# computer.net
KiCad netlist of a schematic drawn in Altium Designer
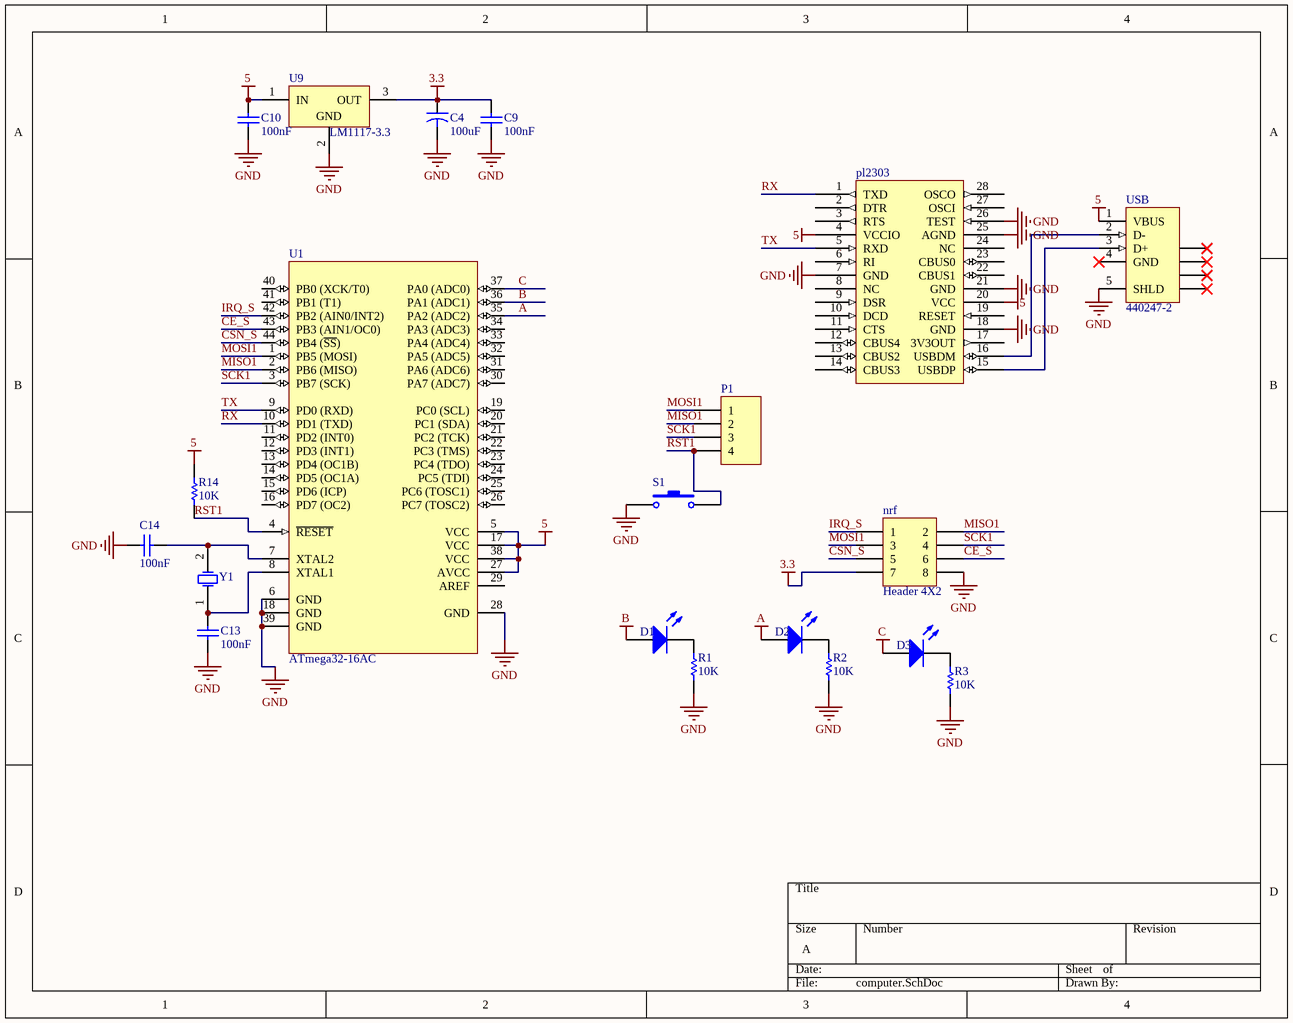
[diagram p0: computer.SchDoc]

(export (version "E")
  (design (tool "Eeschema 10.0.6"))
  (components
    (comp (ref "C4")
      (value "100uF")
      (footprint "cap")
      (description "Capacitor")
      (fields (field (name "Comment") "Cap2") (field (name "PUBLISHER") "Altium Limited"))
      (libsource (lib "Miscellaneous Devices") (part "Cap2"))
    )
    (comp (ref "C9")
      (value "100nF")
      (footprint "H1X02F")
      (description "Capacitor")
      (fields (field (name "Comment") "Cap") (field (name "PUBLISHER") "Altium Limited"))
      (libsource (lib "Miscellaneous Devices") (part "Cap"))
    )
    (comp (ref "C10")
      (value "100nF")
      (footprint "H1X02F")
      (description "Capacitor")
      (fields (field (name "Comment") "Cap") (field (name "PUBLISHER") "Altium Limited"))
      (libsource (lib "Miscellaneous Devices") (part "Cap"))
    )
    (comp (ref "C13")
      (value "100nF")
      (footprint "H1X02F")
      (description "Capacitor")
      (fields (field (name "Comment") "Cap") (field (name "PUBLISHER") "Altium Limited"))
      (libsource (lib "Miscellaneous Devices") (part "Cap"))
    )
    (comp (ref "C14")
      (value "100nF")
      (footprint "H1X02F")
      (description "Capacitor")
      (fields (field (name "Comment") "Cap") (field (name "PUBLISHER") "Altium Limited"))
      (libsource (lib "Miscellaneous Devices") (part "Cap"))
    )
    (comp (ref "D1")
      (value "LED0")
      (footprint "LED3MM")
      (description "Typical INFRARED GaAs LED")
      (fields (field (name "PUBLISHER") "Altium Limited"))
      (libsource (lib "Miscellaneous Devices") (part "LED0"))
    )
    (comp (ref "D2")
      (value "LED0")
      (footprint "LED3MM")
      (description "Typical INFRARED GaAs LED")
      (fields (field (name "PUBLISHER") "Altium Limited"))
      (libsource (lib "Miscellaneous Devices") (part "LED0"))
    )
    (comp (ref "D3")
      (value "LED0")
      (footprint "LED3MM")
      (description "Typical INFRARED GaAs LED")
      (fields (field (name "PUBLISHER") "Altium Limited"))
      (libsource (lib "Miscellaneous Devices") (part "LED0"))
    )
    (comp (ref "nrf")
      (value "Header 4X2")
      (footprint "HDR2X4")
      (description "Header, 4-Pin, Dual row")
      (fields (field (name "PUBLISHER") "Altium Limited"))
      (libsource (lib "Miscellaneous Connectors") (part "Header 4X2"))
    )
    (comp (ref "P1")
      (value "Header 4")
      (footprint "H1X04F")
      (description "Header, 4-Pin")
      (fields (field (name "PUBLISHER") "Altium Limited"))
      (libsource (lib "Miscellaneous Connectors") (part "Header 4"))
    )
    (comp (ref "pl2303")
      (value "pl2303")
      (footprint "SSOP28")
      (description "ft232rl USB <> UART")
      (libsource (lib "ft232rl") (part "ft232rl"))
    )
    (comp (ref "R1")
      (value "10K")
      (footprint "smd[1206]")
      (description "Resistor")
      (fields (field (name "Comment") "Res1") (field (name "PUBLISHER") "Altium Limited"))
      (libsource (lib "Miscellaneous Devices") (part "Res1"))
    )
    (comp (ref "R2")
      (value "10K")
      (footprint "smd[1206]")
      (description "Resistor")
      (fields (field (name "Comment") "Res1") (field (name "PUBLISHER") "Altium Limited"))
      (libsource (lib "Miscellaneous Devices") (part "Res1"))
    )
    (comp (ref "R3")
      (value "10K")
      (footprint "smd[1206]")
      (description "Resistor")
      (fields (field (name "Comment") "Res1") (field (name "PUBLISHER") "Altium Limited"))
      (libsource (lib "Miscellaneous Devices") (part "Res1"))
    )
    (comp (ref "R14")
      (value "10K")
      (footprint "AXIAL-0.3")
      (description "Resistor")
      (fields (field (name "Comment") "Res1") (field (name "PUBLISHER") "Altium Limited"))
      (libsource (lib "Miscellaneous Devices") (part "Res1"))
    )
    (comp (ref "S1")
      (value "SW-PB")
      (footprint "PB4")
      (description "Switch")
      (fields (field (name "PUBLISHER") "Altium Limited"))
      (libsource (lib "Miscellaneous Devices") (part "SW-PB"))
    )
    (comp (ref "U1")
      (value "ATmega32-16AC")
      (footprint "TQFP44")
      (description "8-Bit AVR Microcontroller with 32K Bytes of In-System Programmable Flash Memory")
      (fields (field (name "PUBLISHER") "Altium Limited"))
      (libsource (lib "Atmel Microcontroller 8-Bit AVR") (part "ATmega32-16AC"))
    )
    (comp (ref "U9")
      (value "LM1117-3.3")
      (footprint "SOT223")
      (description "500mA, Very Low Drop (0.45V) Voltage Regulator")
      (fields (field (name "PUBLISHER") "Altium Limited"))
      (libsource (lib "ST Power Mgt Voltage Regulator") (part "LF33ABV"))
    )
    (comp (ref "USB")
      (value "440247-2")
      (footprint "MiniUSB-B")
      (description "USB 2.0, Right Angle, SMT, B Type, Receptacle, 5 Position, Black")
      (fields (field (name "PUBLISHER") "Altium Limited"))
      (libsource (lib "AMP Serial Bus USB") (part "440247-2"))
    )
    (comp (ref "Y1")
      (value "XTAL")
      (footprint "CRYSTALL")
      (description "Crystal Oscillator")
      (fields (field (name "PUBLISHER") "Altium Limited"))
      (libsource (lib "Miscellaneous Devices") (part "XTAL"))
    )
  )
  (nets
    (net (code "1") (name "/CE_S") (class "Default")
      (node (ref "U1") (pin "43") (pinfunction "PB3_(AIN1/OC0)_43") (pintype "bidirectional"))
      (node (ref "nrf") (pin "6") (pinfunction "6_6") (pintype "passive"))
    )
    (net (code "2") (name "/CSN_S") (class "Default")
      (node (ref "U1") (pin "44") (pinfunction "PB4_(~{SS})_44") (pintype "bidirectional"))
      (node (ref "nrf") (pin "5") (pinfunction "5_5") (pintype "passive"))
    )
    (net (code "3") (name "/IRQ_S") (class "Default")
      (node (ref "U1") (pin "42") (pinfunction "PB2_(AIN0/INT2)_42") (pintype "bidirectional"))
      (node (ref "nrf") (pin "1") (pinfunction "1_1") (pintype "passive"))
    )
    (net (code "4") (name "/MISO1") (class "Default")
      (node (ref "P1") (pin "2") (pinfunction "2_2") (pintype "passive"))
      (node (ref "U1") (pin "2") (pinfunction "PB6_(MISO)_2") (pintype "bidirectional"))
      (node (ref "nrf") (pin "2") (pinfunction "2_2") (pintype "passive"))
    )
    (net (code "5") (name "/MOSI1") (class "Default")
      (node (ref "P1") (pin "1") (pinfunction "1_1") (pintype "passive"))
      (node (ref "U1") (pin "1") (pinfunction "PB5_(MOSI)_1") (pintype "bidirectional"))
      (node (ref "nrf") (pin "3") (pinfunction "3_3") (pintype "passive"))
    )
    (net (code "6") (name "/RST1") (class "Default")
      (node (ref "P1") (pin "4") (pinfunction "4_4") (pintype "passive"))
      (node (ref "R14") (pin "2") (pinfunction "2_2") (pintype "passive"))
      (node (ref "S1") (pin "2") (pinfunction "2_2") (pintype "passive"))
      (node (ref "U1") (pin "4") (pinfunction "~{RESET}_4") (pintype "input"))
    )
    (net (code "7") (name "/RX") (class "Default")
      (node (ref "U1") (pin "10") (pinfunction "PD1_(TXD)_10") (pintype "bidirectional"))
      (node (ref "pl2303") (pin "1") (pinfunction "TXD_1") (pintype "output"))
    )
    (net (code "8") (name "/SCK1") (class "Default")
      (node (ref "P1") (pin "3") (pinfunction "3_3") (pintype "passive"))
      (node (ref "U1") (pin "3") (pinfunction "PB7_(SCK)_3") (pintype "bidirectional"))
      (node (ref "nrf") (pin "4") (pinfunction "4_4") (pintype "passive"))
    )
    (net (code "9") (name "/TX") (class "Default")
      (node (ref "U1") (pin "9") (pinfunction "PD0_(RXD)_9") (pintype "bidirectional"))
      (node (ref "pl2303") (pin "5") (pinfunction "RXD_5") (pintype "input"))
    )
    (net (code "10") (name "3.3") (class "Default")
      (node (ref "C4") (pin "1") (pinfunction "1_1") (pintype "passive"))
      (node (ref "C9") (pin "1") (pinfunction "1_1") (pintype "passive"))
      (node (ref "U9") (pin "3") (pinfunction "OUT_3") (pintype "power_in"))
      (node (ref "nrf") (pin "7") (pinfunction "7_7") (pintype "passive"))
    )
    (net (code "11") (name "5") (class "Default")
      (node (ref "C10") (pin "1") (pinfunction "1_1") (pintype "passive"))
      (node (ref "R14") (pin "1") (pinfunction "1_1") (pintype "passive"))
      (node (ref "U1") (pin "17") (pinfunction "VCC_17") (pintype "power_in"))
      (node (ref "U1") (pin "27") (pinfunction "AVCC_27") (pintype "power_in"))
      (node (ref "U1") (pin "38") (pinfunction "VCC_38") (pintype "power_in"))
      (node (ref "U1") (pin "5") (pinfunction "VCC_5") (pintype "power_in"))
      (node (ref "U9") (pin "1") (pinfunction "IN_1") (pintype "power_in"))
      (node (ref "USB") (pin "1") (pinfunction "VBUS_1") (pintype "power_in"))
      (node (ref "pl2303") (pin "20") (pinfunction "VCC_20") (pintype "power_in"))
      (node (ref "pl2303") (pin "4") (pinfunction "VCCIO_4") (pintype "power_in"))
    )
    (net (code "12") (name "A") (class "Default")
      (node (ref "D2") (pin "1") (pinfunction "A_1") (pintype "passive"))
      (node (ref "U1") (pin "35") (pinfunction "PA2_(ADC2)_35") (pintype "bidirectional"))
    )
    (net (code "13") (name "B") (class "Default")
      (node (ref "D1") (pin "1") (pinfunction "A_1") (pintype "passive"))
      (node (ref "U1") (pin "36") (pinfunction "PA1_(ADC1)_36") (pintype "bidirectional"))
    )
    (net (code "14") (name "C") (class "Default")
      (node (ref "D3") (pin "1") (pinfunction "A_1") (pintype "passive"))
      (node (ref "U1") (pin "37") (pinfunction "PA0_(ADC0)_37") (pintype "bidirectional"))
    )
    (net (code "15") (name "GND") (class "Default")
      (node (ref "C10") (pin "2") (pinfunction "2_2") (pintype "passive"))
      (node (ref "C13") (pin "2") (pinfunction "2_2") (pintype "passive"))
      (node (ref "C14") (pin "1") (pinfunction "1_1") (pintype "passive"))
      (node (ref "C4") (pin "2") (pinfunction "2_2") (pintype "passive"))
      (node (ref "C9") (pin "2") (pinfunction "2_2") (pintype "passive"))
      (node (ref "R1") (pin "1") (pinfunction "1_1") (pintype "passive"))
      (node (ref "R2") (pin "1") (pinfunction "1_1") (pintype "passive"))
      (node (ref "R3") (pin "1") (pinfunction "1_1") (pintype "passive"))
      (node (ref "S1") (pin "1") (pinfunction "1_1") (pintype "passive"))
      (node (ref "U1") (pin "18") (pinfunction "GND_18") (pintype "power_in"))
      (node (ref "U1") (pin "28") (pinfunction "GND_28") (pintype "power_in"))
      (node (ref "U1") (pin "39") (pinfunction "GND_39") (pintype "power_in"))
      (node (ref "U1") (pin "6") (pinfunction "GND_6") (pintype "power_in"))
      (node (ref "U9") (pin "2") (pinfunction "GND_2") (pintype "power_in"))
      (node (ref "USB") (pin "5") (pinfunction "SHLD_5") (pintype "passive"))
      (node (ref "nrf") (pin "8") (pinfunction "8_8") (pintype "passive"))
      (node (ref "pl2303") (pin "18") (pinfunction "GND_18") (pintype "power_in"))
      (node (ref "pl2303") (pin "21") (pinfunction "GND_21") (pintype "power_in"))
      (node (ref "pl2303") (pin "25") (pinfunction "AGND_25") (pintype "power_in"))
      (node (ref "pl2303") (pin "26") (pinfunction "TEST_26") (pintype "input"))
      (node (ref "pl2303") (pin "7") (pinfunction "GND_7") (pintype "power_in"))
    )
    (net (code "16") (name "Net-(D1-K)") (class "Default")
      (node (ref "D1") (pin "2") (pinfunction "K_2") (pintype "passive"))
      (node (ref "R1") (pin "2") (pinfunction "2_2") (pintype "passive"))
    )
    (net (code "17") (name "Net-(D2-K)") (class "Default")
      (node (ref "D2") (pin "2") (pinfunction "K_2") (pintype "passive"))
      (node (ref "R2") (pin "2") (pinfunction "2_2") (pintype "passive"))
    )
    (net (code "18") (name "Net-(D3-K)") (class "Default")
      (node (ref "D3") (pin "2") (pinfunction "K_2") (pintype "passive"))
      (node (ref "R3") (pin "2") (pinfunction "2_2") (pintype "passive"))
    )
    (net (code "19") (name "Net-(U1-XTAL1)") (class "Default")
      (node (ref "C13") (pin "1") (pinfunction "1_1") (pintype "passive"))
      (node (ref "U1") (pin "8") (pinfunction "XTAL1_8") (pintype "passive"))
      (node (ref "Y1") (pin "1") (pinfunction "OSC1_1") (pintype "passive"))
    )
    (net (code "20") (name "Net-(U1-XTAL2)") (class "Default")
      (node (ref "C14") (pin "2") (pinfunction "2_2") (pintype "passive"))
      (node (ref "U1") (pin "7") (pinfunction "XTAL2_7") (pintype "passive"))
      (node (ref "Y1") (pin "2") (pinfunction "OSC2_2") (pintype "passive"))
    )
    (net (code "21") (name "Net-(USB-D+)") (class "Default")
      (node (ref "USB") (pin "3") (pinfunction "D+_3") (pintype "input"))
      (node (ref "pl2303") (pin "15") (pinfunction "USBDP_15") (pintype "bidirectional"))
    )
    (net (code "22") (name "Net-(USB-D-)") (class "Default")
      (node (ref "USB") (pin "2") (pinfunction "D-_2") (pintype "input"))
      (node (ref "pl2303") (pin "16") (pinfunction "USBDM_16") (pintype "bidirectional"))
    )
    (net (code "23") (name "unconnected-(U1-AREF-Pad29)") (class "Default")
      (node (ref "U1") (pin "29") (pinfunction "AREF_29") (pintype "passive"))
    )
    (net (code "24") (name "unconnected-(U1-PA3_(ADC3)-Pad34)") (class "Default")
      (node (ref "U1") (pin "34") (pinfunction "PA3_(ADC3)_34") (pintype "bidirectional"))
    )
    (net (code "25") (name "unconnected-(U1-PA4_(ADC4)-Pad33)") (class "Default")
      (node (ref "U1") (pin "33") (pinfunction "PA4_(ADC4)_33") (pintype "bidirectional"))
    )
    (net (code "26") (name "unconnected-(U1-PA5_(ADC5)-Pad32)") (class "Default")
      (node (ref "U1") (pin "32") (pinfunction "PA5_(ADC5)_32") (pintype "bidirectional"))
    )
    (net (code "27") (name "unconnected-(U1-PA6_(ADC6)-Pad31)") (class "Default")
      (node (ref "U1") (pin "31") (pinfunction "PA6_(ADC6)_31") (pintype "bidirectional"))
    )
    (net (code "28") (name "unconnected-(U1-PA7_(ADC7)-Pad30)") (class "Default")
      (node (ref "U1") (pin "30") (pinfunction "PA7_(ADC7)_30") (pintype "bidirectional"))
    )
    (net (code "29") (name "unconnected-(U1-PB0_(XCK{slash}T0)-Pad40)") (class "Default")
      (node (ref "U1") (pin "40") (pinfunction "PB0_(XCK/T0)_40") (pintype "bidirectional"))
    )
    (net (code "30") (name "unconnected-(U1-PB1_(T1)-Pad41)") (class "Default")
      (node (ref "U1") (pin "41") (pinfunction "PB1_(T1)_41") (pintype "bidirectional"))
    )
    (net (code "31") (name "unconnected-(U1-PC0_(SCL)-Pad19)") (class "Default")
      (node (ref "U1") (pin "19") (pinfunction "PC0_(SCL)_19") (pintype "bidirectional"))
    )
    (net (code "32") (name "unconnected-(U1-PC1_(SDA)-Pad20)") (class "Default")
      (node (ref "U1") (pin "20") (pinfunction "PC1_(SDA)_20") (pintype "bidirectional"))
    )
    (net (code "33") (name "unconnected-(U1-PC2_(TCK)-Pad21)") (class "Default")
      (node (ref "U1") (pin "21") (pinfunction "PC2_(TCK)_21") (pintype "bidirectional"))
    )
    (net (code "34") (name "unconnected-(U1-PC3_(TMS)-Pad22)") (class "Default")
      (node (ref "U1") (pin "22") (pinfunction "PC3_(TMS)_22") (pintype "bidirectional"))
    )
    (net (code "35") (name "unconnected-(U1-PC4_(TDO)-Pad23)") (class "Default")
      (node (ref "U1") (pin "23") (pinfunction "PC4_(TDO)_23") (pintype "bidirectional"))
    )
    (net (code "36") (name "unconnected-(U1-PC5_(TDI)-Pad24)") (class "Default")
      (node (ref "U1") (pin "24") (pinfunction "PC5_(TDI)_24") (pintype "bidirectional"))
    )
    (net (code "37") (name "unconnected-(U1-PC6_(TOSC1)-Pad25)") (class "Default")
      (node (ref "U1") (pin "25") (pinfunction "PC6_(TOSC1)_25") (pintype "bidirectional"))
    )
    (net (code "38") (name "unconnected-(U1-PC7_(TOSC2)-Pad26)") (class "Default")
      (node (ref "U1") (pin "26") (pinfunction "PC7_(TOSC2)_26") (pintype "bidirectional"))
    )
    (net (code "39") (name "unconnected-(U1-PD2_(INT0)-Pad11)") (class "Default")
      (node (ref "U1") (pin "11") (pinfunction "PD2_(INT0)_11") (pintype "bidirectional"))
    )
    (net (code "40") (name "unconnected-(U1-PD3_(INT1)-Pad12)") (class "Default")
      (node (ref "U1") (pin "12") (pinfunction "PD3_(INT1)_12") (pintype "bidirectional"))
    )
    (net (code "41") (name "unconnected-(U1-PD4_(OC1B)-Pad13)") (class "Default")
      (node (ref "U1") (pin "13") (pinfunction "PD4_(OC1B)_13") (pintype "bidirectional"))
    )
    (net (code "42") (name "unconnected-(U1-PD5_(OC1A)-Pad14)") (class "Default")
      (node (ref "U1") (pin "14") (pinfunction "PD5_(OC1A)_14") (pintype "bidirectional"))
    )
    (net (code "43") (name "unconnected-(U1-PD6_(ICP)-Pad15)") (class "Default")
      (node (ref "U1") (pin "15") (pinfunction "PD6_(ICP)_15") (pintype "bidirectional"))
    )
    (net (code "44") (name "unconnected-(U1-PD7_(OC2)-Pad16)") (class "Default")
      (node (ref "U1") (pin "16") (pinfunction "PD7_(OC2)_16") (pintype "bidirectional"))
    )
    (net (code "45") (name "unconnected-(USB-GND-Pad4)") (class "Default")
      (node (ref "USB") (pin "4") (pinfunction "GND_4") (pintype "power_in+no_connect"))
    )
    (net (code "46") (name "unconnected-(USB-SHLD-Pad6)") (class "Default")
      (node (ref "USB") (pin "6") (pinfunction "SHLD_6") (pintype "passive+no_connect"))
    )
    (net (code "47") (name "unconnected-(USB-SHLD-Pad7)") (class "Default")
      (node (ref "USB") (pin "7") (pinfunction "SHLD_7") (pintype "passive+no_connect"))
    )
    (net (code "48") (name "unconnected-(USB-SHLD-Pad8)") (class "Default")
      (node (ref "USB") (pin "8") (pinfunction "SHLD_8") (pintype "passive+no_connect"))
    )
    (net (code "49") (name "unconnected-(USB-SHLD-Pad9)") (class "Default")
      (node (ref "USB") (pin "9") (pinfunction "SHLD_9") (pintype "passive+no_connect"))
    )
    (net (code "50") (name "unconnected-(pl2303-3V3OUT-Pad17)") (class "Default")
      (node (ref "pl2303") (pin "17") (pinfunction "3V3OUT_17") (pintype "output"))
    )
    (net (code "51") (name "unconnected-(pl2303-CBUS0-Pad23)") (class "Default")
      (node (ref "pl2303") (pin "23") (pinfunction "CBUS0_23") (pintype "bidirectional"))
    )
    (net (code "52") (name "unconnected-(pl2303-CBUS1-Pad22)") (class "Default")
      (node (ref "pl2303") (pin "22") (pinfunction "CBUS1_22") (pintype "bidirectional"))
    )
    (net (code "53") (name "unconnected-(pl2303-CBUS2-Pad13)") (class "Default")
      (node (ref "pl2303") (pin "13") (pinfunction "CBUS2_13") (pintype "bidirectional"))
    )
    (net (code "54") (name "unconnected-(pl2303-CBUS3-Pad14)") (class "Default")
      (node (ref "pl2303") (pin "14") (pinfunction "CBUS3_14") (pintype "bidirectional"))
    )
    (net (code "55") (name "unconnected-(pl2303-CBUS4-Pad12)") (class "Default")
      (node (ref "pl2303") (pin "12") (pinfunction "CBUS4_12") (pintype "bidirectional"))
    )
    (net (code "56") (name "unconnected-(pl2303-CTS-Pad11)") (class "Default")
      (node (ref "pl2303") (pin "11") (pinfunction "CTS_11") (pintype "input"))
    )
    (net (code "57") (name "unconnected-(pl2303-DCD-Pad10)") (class "Default")
      (node (ref "pl2303") (pin "10") (pinfunction "DCD_10") (pintype "input"))
    )
    (net (code "58") (name "unconnected-(pl2303-DSR-Pad9)") (class "Default")
      (node (ref "pl2303") (pin "9") (pinfunction "DSR_9") (pintype "input"))
    )
    (net (code "59") (name "unconnected-(pl2303-DTR-Pad2)") (class "Default")
      (node (ref "pl2303") (pin "2") (pinfunction "DTR_2") (pintype "output"))
    )
    (net (code "60") (name "unconnected-(pl2303-NC-Pad8)") (class "Default")
      (node (ref "pl2303") (pin "8") (pinfunction "NC_8") (pintype "open_collector"))
    )
    (net (code "61") (name "unconnected-(pl2303-NC-Pad24)") (class "Default")
      (node (ref "pl2303") (pin "24") (pinfunction "NC_24") (pintype "open_collector"))
    )
    (net (code "62") (name "unconnected-(pl2303-OSCI-Pad27)") (class "Default")
      (node (ref "pl2303") (pin "27") (pinfunction "OSCI_27") (pintype "input"))
    )
    (net (code "63") (name "unconnected-(pl2303-OSCO-Pad28)") (class "Default")
      (node (ref "pl2303") (pin "28") (pinfunction "OSCO_28") (pintype "output"))
    )
    (net (code "64") (name "unconnected-(pl2303-RESET-Pad19)") (class "Default")
      (node (ref "pl2303") (pin "19") (pinfunction "RESET_19") (pintype "input"))
    )
    (net (code "65") (name "unconnected-(pl2303-RI-Pad6)") (class "Default")
      (node (ref "pl2303") (pin "6") (pinfunction "RI_6") (pintype "input"))
    )
    (net (code "66") (name "unconnected-(pl2303-RTS-Pad3)") (class "Default")
      (node (ref "pl2303") (pin "3") (pinfunction "RTS_3") (pintype "output"))
    )
  )
)
